# f1-control.net
KiCad netlist of a schematic drawn in EasyEDA Pro
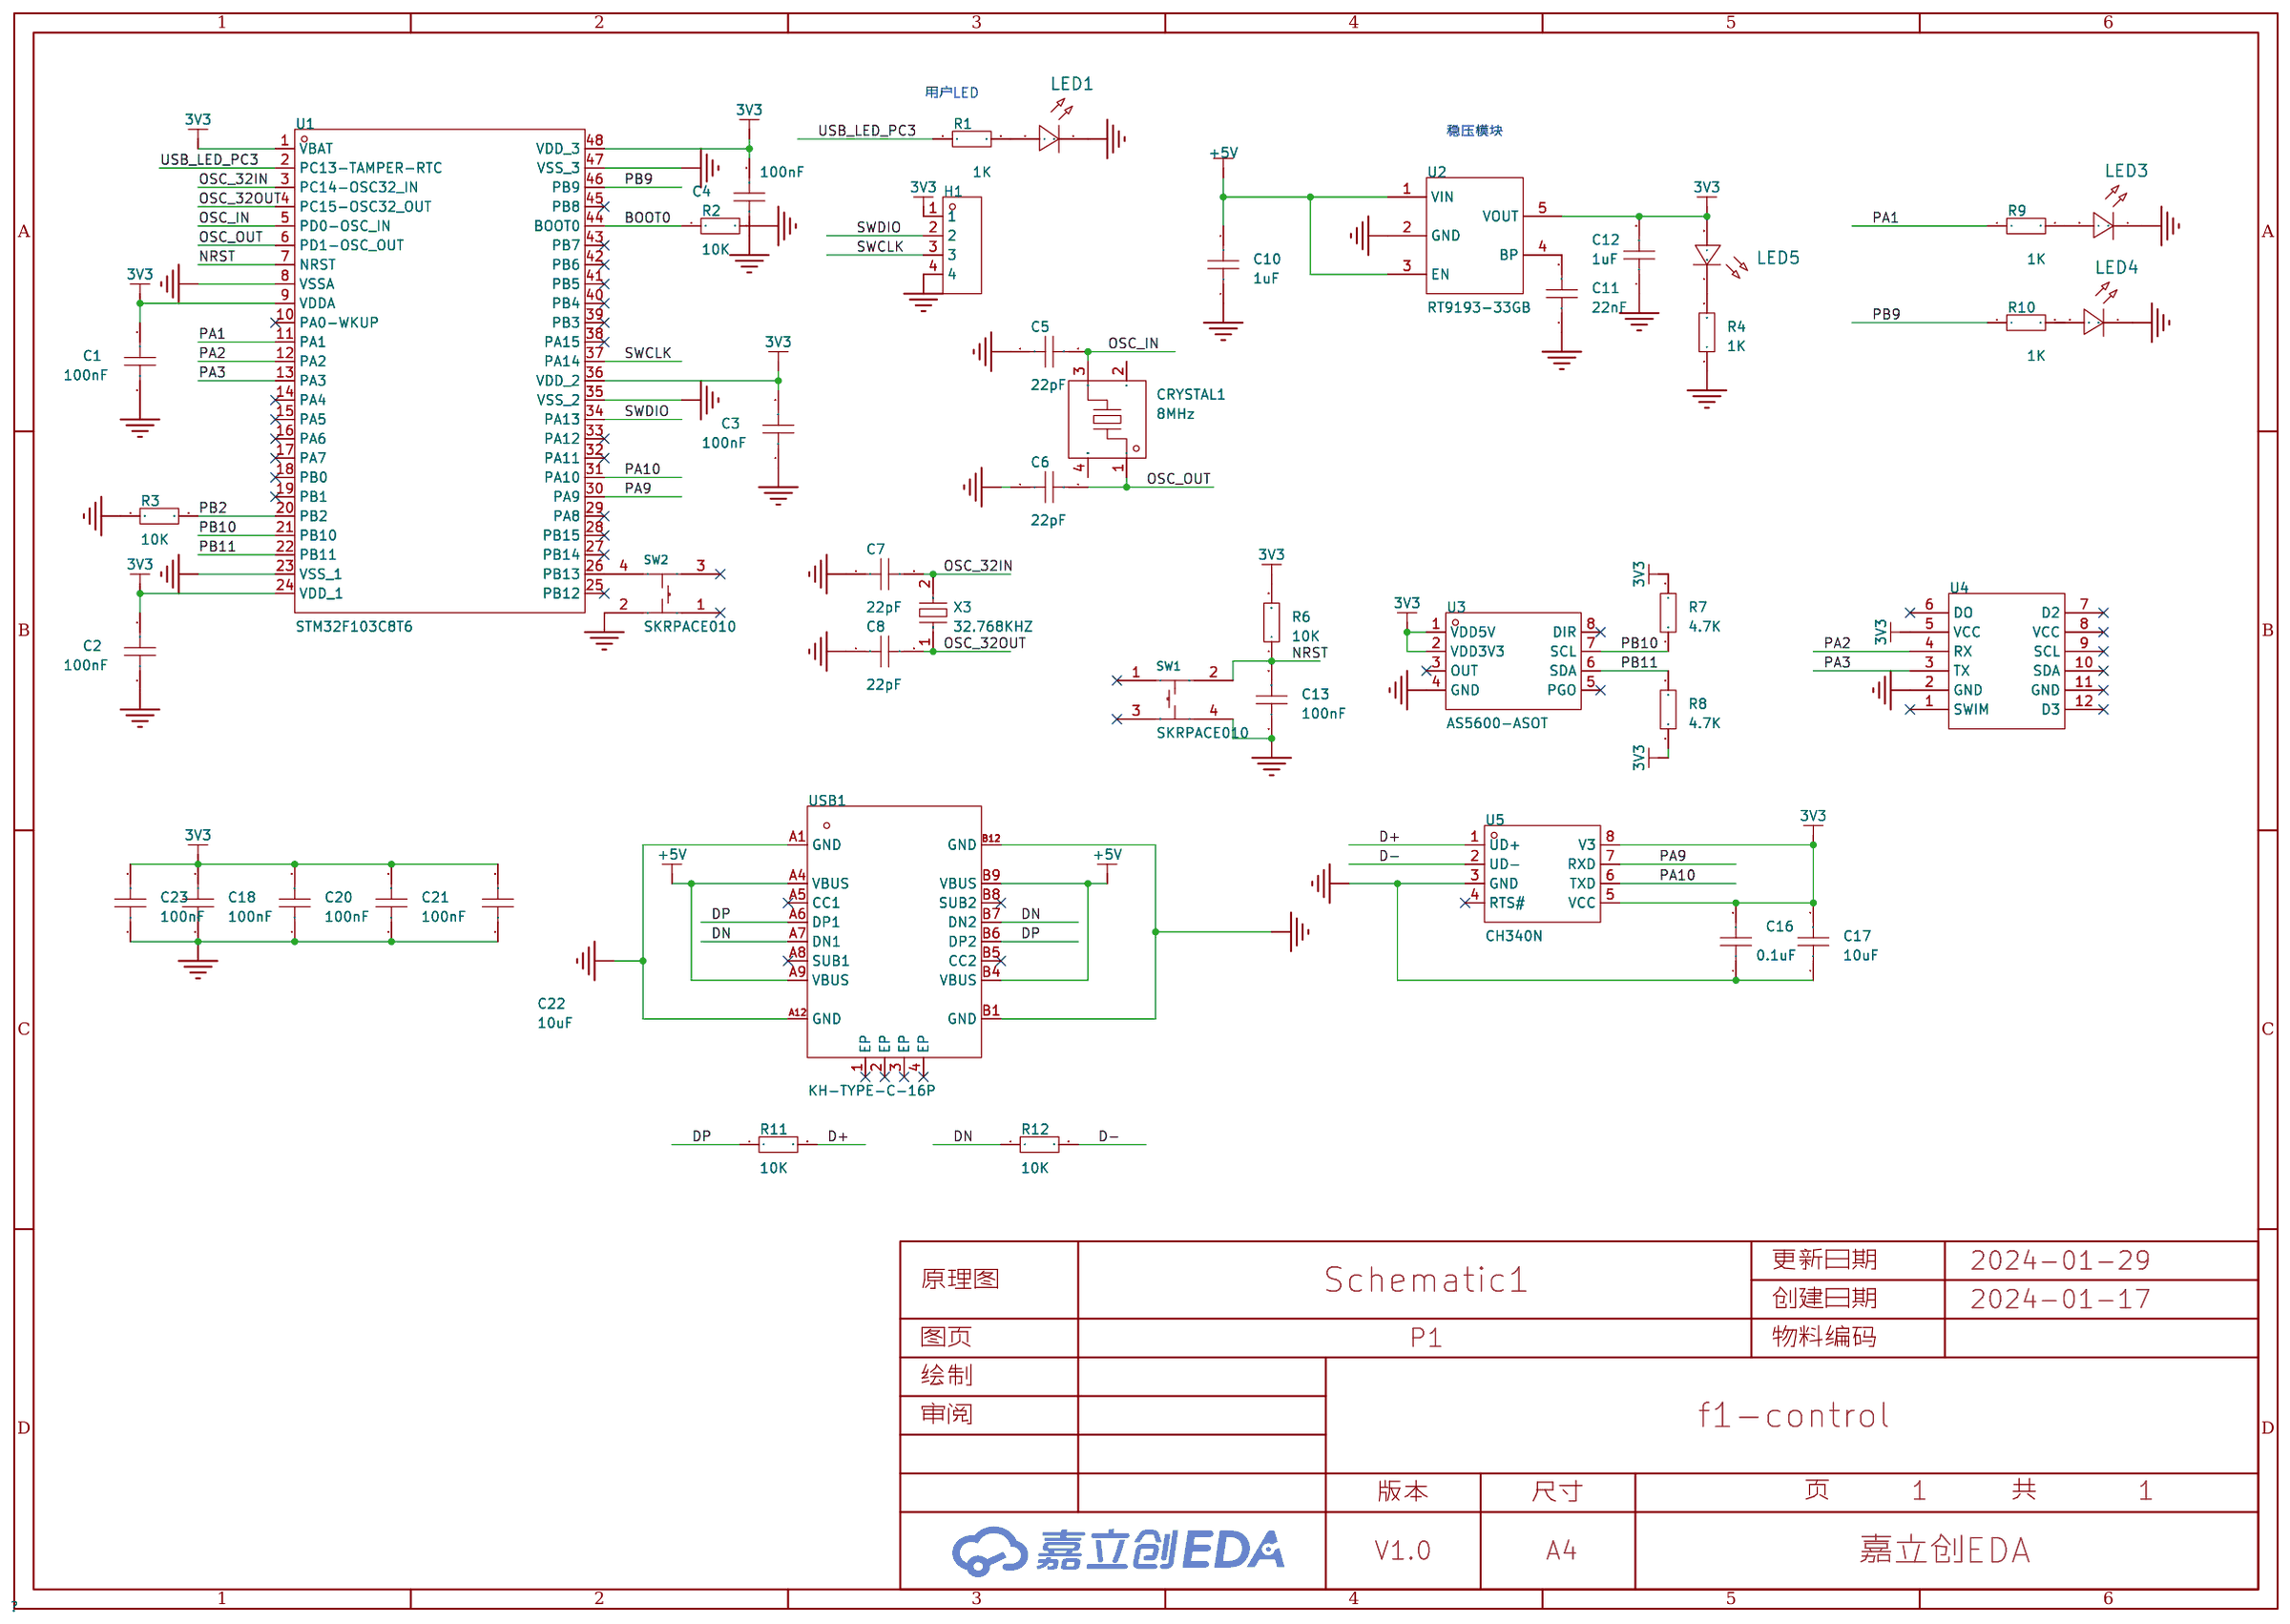
[diagram p0: schematic sheet]

(export (version "E")
  (design (tool "Eeschema 10.0.6"))
  (components
    (comp (ref "C1")
      (value "100nF")
      (footprint "easyedapro:C0603")
      (libsource (lib "easyedapro") (part "CapAcitance"))
    )
    (comp (ref "C2")
      (value "100nF")
      (footprint "easyedapro:C0603")
      (libsource (lib "easyedapro") (part "CapAcitance"))
    )
    (comp (ref "C3")
      (value "100nF")
      (footprint "easyedapro:C0603")
      (libsource (lib "easyedapro") (part "CapAcitance"))
    )
    (comp (ref "C4")
      (value "100nF")
      (footprint "easyedapro:C0603")
      (libsource (lib "easyedapro") (part "CapAcitance"))
    )
    (comp (ref "C5")
      (value "22pF")
      (footprint "easyedapro:C0603")
      (libsource (lib "easyedapro") (part "CapAcitance"))
    )
    (comp (ref "C6")
      (value "22pF")
      (footprint "easyedapro:C0603")
      (libsource (lib "easyedapro") (part "CapAcitance"))
    )
    (comp (ref "C7")
      (value "22pF")
      (footprint "easyedapro:C0603")
      (libsource (lib "easyedapro") (part "CapAcitance"))
    )
    (comp (ref "C8")
      (value "22pF")
      (footprint "easyedapro:C0603")
      (libsource (lib "easyedapro") (part "CapAcitance"))
    )
    (comp (ref "C10")
      (value "1uF")
      (footprint "easyedapro:C0603")
      (libsource (lib "easyedapro") (part "CapAcitance"))
    )
    (comp (ref "C11")
      (value "22nF")
      (footprint "easyedapro:C0603")
      (libsource (lib "easyedapro") (part "CapAcitance"))
    )
    (comp (ref "C12")
      (value "1uF")
      (footprint "easyedapro:C0603")
      (libsource (lib "easyedapro") (part "CapAcitance"))
    )
    (comp (ref "C13")
      (value "100nF")
      (footprint "easyedapro:C0603")
      (libsource (lib "easyedapro") (part "CapAcitance"))
    )
    (comp (ref "C16")
      (value "0.1uF")
      (footprint "easyedapro:C0603")
      (libsource (lib "easyedapro") (part "CapAcitance"))
    )
    (comp (ref "C17")
      (value "10uF")
      (footprint "easyedapro:C0603")
      (libsource (lib "easyedapro") (part "CapAcitance"))
    )
    (comp (ref "C18")
      (value "100nF")
      (footprint "easyedapro:C0603")
      (libsource (lib "easyedapro") (part "CapAcitance"))
    )
    (comp (ref "C20")
      (value "100nF")
      (footprint "easyedapro:C0603")
      (libsource (lib "easyedapro") (part "CapAcitance"))
    )
    (comp (ref "C21")
      (value "100nF")
      (footprint "easyedapro:C0603")
      (libsource (lib "easyedapro") (part "CapAcitance"))
    )
    (comp (ref "C22")
      (value "10uF")
      (footprint "easyedapro:C0603")
      (libsource (lib "easyedapro") (part "CapAcitance"))
    )
    (comp (ref "C23")
      (value "100nF")
      (footprint "easyedapro:C0603")
      (libsource (lib "easyedapro") (part "CapAcitance"))
    )
    (comp (ref "CRYSTAL1")
      (value "8MHz")
      (footprint "easyedapro:CRYSTAL-SMD_4P-L3.2-W2.5-BL_SIT8008BI")
      (description "晶振类型:贴片晶振;频率:8MHz;常温频差:±10ppm;外接负载电容:12pF;频率稳定度(全温):±30ppm;")
      (fields (field (name "Manufacturer Part") "CF4008M00012001") (field (name "Manufacturer") "HUAXIN(华昕)"))
      (libsource (lib "easyedapro") (part "CF4008M00012001"))
    )
    (comp (ref "H1")
      (value "~")
      (footprint "easyedapro:HDR-TH_4P-P2.54-V-F")
      (libsource (lib "easyedapro") (part "2.54-1*4P母"))
    )
    (comp (ref "LED1")
      (value "~")
      (footprint "easyedapro:LED_0603")
      (libsource (lib "easyedapro") (part "LED_R"))
    )
    (comp (ref "LED3")
      (value "~")
      (footprint "easyedapro:LED_0603")
      (libsource (lib "easyedapro") (part "LED_R"))
    )
    (comp (ref "LED4")
      (value "~")
      (footprint "easyedapro:LED_0603")
      (libsource (lib "easyedapro") (part "LED_R"))
    )
    (comp (ref "LED5")
      (value "~")
      (footprint "easyedapro:LED_0603")
      (libsource (lib "easyedapro") (part "LED_R"))
    )
    (comp (ref "R1") (value "1K") (footprint "easyedapro:R0603") (libsource (lib "easyedapro") (part "电阻")))
    (comp (ref "R2") (value "10K") (footprint "easyedapro:R0603") (libsource (lib "easyedapro") (part "电阻")))
    (comp (ref "R3") (value "10K") (footprint "easyedapro:R0603") (libsource (lib "easyedapro") (part "电阻")))
    (comp (ref "R4") (value "1K") (footprint "easyedapro:R0603") (libsource (lib "easyedapro") (part "电阻")))
    (comp (ref "R6") (value "10K") (footprint "easyedapro:R0603") (libsource (lib "easyedapro") (part "电阻")))
    (comp (ref "R7") (value "4.7K") (footprint "easyedapro:R0603") (libsource (lib "easyedapro") (part "电阻")))
    (comp (ref "R8") (value "4.7K") (footprint "easyedapro:R0603") (libsource (lib "easyedapro") (part "电阻")))
    (comp (ref "R9") (value "1K") (footprint "easyedapro:R0603") (libsource (lib "easyedapro") (part "电阻")))
    (comp (ref "R10") (value "1K") (footprint "easyedapro:R0603") (libsource (lib "easyedapro") (part "电阻")))
    (comp (ref "R11") (value "10K") (footprint "easyedapro:R0603") (libsource (lib "easyedapro") (part "电阻")))
    (comp (ref "R12") (value "10K") (footprint "easyedapro:R0603") (libsource (lib "easyedapro") (part "电阻")))
    (comp (ref "SW1")
      (value "SKRPACE010")
      (footprint "easyedapro:KEY-SMD_4P-L4.2-W3.2-P2.20-LS4.6")
      (description "触点电流:50mA;额定电压(DC):16V;电路结构:单刀单掷;安装方式:立贴;带灯:-;机械寿命:-;")
      (fields (field (name "Manufacturer") "ALPSALPINE(阿尔卑斯阿尔派)"))
      (libsource (lib "easyedapro") (part "SKRPACE010"))
    )
    (comp (ref "SW2")
      (value "SKRPACE010")
      (footprint "easyedapro:KEY-SMD_4P-L4.2-W3.2-P2.20-LS4.6")
      (description "触点电流:50mA;额定电压(DC):16V;电路结构:单刀单掷;安装方式:立贴;带灯:-;机械寿命:-;")
      (fields (field (name "Manufacturer") "ALPSALPINE(阿尔卑斯阿尔派)"))
      (libsource (lib "easyedapro") (part "SKRPACE010"))
    )
    (comp (ref "U1")
      (value "STM32F103C8T6")
      (footprint "easyedapro:LQFP-48_L7.0-W7.0-P0.50-LS9.0-BL")
      (fields (field (name "Manufacturer") "ST(意法半导体)"))
      (libsource (lib "easyedapro") (part "STM32F103C8T6"))
    )
    (comp (ref "U2")
      (value "RT9193-33GB")
      (footprint "easyedapro:SOT-23-5_L3.0-W1.7-P0.95-LS2.8-BL")
      (description "输出类型:固定;最大输入电压:5.5V;输出电压:3.3V;最大输出电流:300mA;电源纹波抑制比(PSRR):70dB;输出极性:正极;")
      (fields (field (name "Manufacturer") "RICHTEK(立锜)"))
      (libsource (lib "easyedapro") (part "RT9193-33GB"))
    )
    (comp (ref "U3")
      (value "AS5600-ASOT")
      (footprint "easyedapro:SOIC-8_L5.0-W4.0-P1.27-LS6.0-BL")
      (fields (field (name "Manufacturer") "ams(艾迈斯半导体)"))
      (libsource (lib "easyedapro") (part "AS5600-ASOT"))
    )
    (comp (ref "U4")
      (value "~")
      (footprint "easyedapro:WT901BC_TYL")
      (libsource (lib "easyedapro") (part "WT901BC_TYL"))
    )
    (comp (ref "U5")
      (value "CH340N")
      (footprint "easyedapro:SOP-8_L5.0-W4.0-P1.27-LS6.0-BL")
      (description "应用功能:-;接口协议:-;")
      (fields (field (name "Manufacturer") "WCH(南京沁恒)"))
      (libsource (lib "easyedapro") (part "CH340N"))
    )
    (comp (ref "USB1")
      (value "KH-TYPE-C-16P")
      (footprint "easyedapro:USB-C-SMD_KH-TYPE-C-16P")
      (description "连接器类型:Type-C;标准:-;公母:母;端口数量:1;触点数量:16P;安装方式:卧贴;额定电流 - 电源:3A;工作温度范围:-40°C~+85°C;")
      (fields (field (name "Manufacturer") "kinghelm(金航标)"))
      (libsource (lib "easyedapro") (part "KH-TYPE-C-16P"))
    )
    (comp (ref "X3")
      (value "32.768KHZ")
      (footprint "easyedapro:CRYSTAL-SMD_L3.2-W1.5-1")
      (libsource (lib "easyedapro") (part "32.768KHZ_C9900023773"))
    )
  )
  (nets
    (net (code "1") (name "+5V") (class "Default")
      (node (ref "C10") (pin "2") (pinfunction "2_2") (pintype "input"))
      (node (ref "U2") (pin "1") (pinfunction "VIN_1") (pintype "unspecified"))
      (node (ref "U2") (pin "3") (pinfunction "EN_3") (pintype "unspecified"))
      (node (ref "USB1") (pin "A4") (pinfunction "VBUS_A4") (pintype "unspecified"))
      (node (ref "USB1") (pin "A9") (pinfunction "VBUS_A9") (pintype "unspecified"))
      (node (ref "USB1") (pin "B4") (pinfunction "VBUS_B4") (pintype "unspecified"))
      (node (ref "USB1") (pin "B9") (pinfunction "VBUS_B9") (pintype "unspecified"))
    )
    (net (code "2") (name "/BOOT0") (class "Default")
      (node (ref "R2") (pin "1") (pinfunction "1_1") (pintype "input"))
      (node (ref "U1") (pin "44") (pinfunction "BOOT0_44") (pintype "unspecified"))
    )
    (net (code "3") (name "/D+") (class "Default")
      (node (ref "R11") (pin "2") (pinfunction "2_2") (pintype "input"))
      (node (ref "U5") (pin "1") (pinfunction "UD+_1") (pintype "unspecified"))
    )
    (net (code "4") (name "/D-") (class "Default")
      (node (ref "R12") (pin "2") (pinfunction "2_2") (pintype "input"))
      (node (ref "U5") (pin "2") (pinfunction "UD-_2") (pintype "unspecified"))
    )
    (net (code "5") (name "/DN") (class "Default")
      (node (ref "R12") (pin "1") (pinfunction "1_1") (pintype "input"))
      (node (ref "USB1") (pin "A7") (pinfunction "DN1_A7") (pintype "unspecified"))
      (node (ref "USB1") (pin "B7") (pinfunction "DN2_B7") (pintype "unspecified"))
    )
    (net (code "6") (name "/DP") (class "Default")
      (node (ref "R11") (pin "1") (pinfunction "1_1") (pintype "input"))
      (node (ref "USB1") (pin "A6") (pinfunction "DP1_A6") (pintype "unspecified"))
      (node (ref "USB1") (pin "B6") (pinfunction "DP2_B6") (pintype "unspecified"))
    )
    (net (code "7") (name "/NRST") (class "Default")
      (node (ref "C13") (pin "2") (pinfunction "2_2") (pintype "input"))
      (node (ref "R6") (pin "1") (pinfunction "1_1") (pintype "input"))
      (node (ref "SW1") (pin "2") (pinfunction "2_2") (pintype "input"))
      (node (ref "U1") (pin "7") (pinfunction "NRST_7") (pintype "unspecified"))
    )
    (net (code "8") (name "/OSC_32IN") (class "Default")
      (node (ref "C7") (pin "2") (pinfunction "2_2") (pintype "input"))
      (node (ref "U1") (pin "3") (pinfunction "PC14-OSC32_IN_3") (pintype "unspecified"))
      (node (ref "X3") (pin "2") (pinfunction "2_2") (pintype "input"))
    )
    (net (code "9") (name "/OSC_32OUT") (class "Default")
      (node (ref "C8") (pin "2") (pinfunction "2_2") (pintype "input"))
      (node (ref "U1") (pin "4") (pinfunction "PC15-OSC32_OUT_4") (pintype "unspecified"))
      (node (ref "X3") (pin "1") (pinfunction "1_1") (pintype "input"))
    )
    (net (code "10") (name "/OSC_IN") (class "Default")
      (node (ref "C5") (pin "2") (pinfunction "2_2") (pintype "input"))
      (node (ref "CRYSTAL1") (pin "3") (pinfunction "3_3") (pintype "input"))
      (node (ref "U1") (pin "5") (pinfunction "PD0-OSC_IN_5") (pintype "unspecified"))
    )
    (net (code "11") (name "/OSC_OUT") (class "Default")
      (node (ref "C6") (pin "2") (pinfunction "2_2") (pintype "input"))
      (node (ref "CRYSTAL1") (pin "1") (pinfunction "1_1") (pintype "input"))
      (node (ref "U1") (pin "6") (pinfunction "PD1-OSC_OUT_6") (pintype "unspecified"))
    )
    (net (code "12") (name "/PA1") (class "Default")
      (node (ref "R9") (pin "1") (pinfunction "1_1") (pintype "input"))
      (node (ref "U1") (pin "11") (pinfunction "PA1_11") (pintype "unspecified"))
    )
    (net (code "13") (name "/PA2") (class "Default")
      (node (ref "U1") (pin "12") (pinfunction "PA2_12") (pintype "unspecified"))
      (node (ref "U4") (pin "4") (pinfunction "RX_4") (pintype "input"))
    )
    (net (code "14") (name "/PA3") (class "Default")
      (node (ref "U1") (pin "13") (pinfunction "PA3_13") (pintype "unspecified"))
      (node (ref "U4") (pin "3") (pinfunction "TX_3") (pintype "input"))
    )
    (net (code "15") (name "/PA9") (class "Default")
      (node (ref "U1") (pin "30") (pinfunction "PA9_30") (pintype "unspecified"))
      (node (ref "U5") (pin "7") (pinfunction "RXD_7") (pintype "unspecified"))
    )
    (net (code "16") (name "/PA10") (class "Default")
      (node (ref "U1") (pin "31") (pinfunction "PA10_31") (pintype "unspecified"))
      (node (ref "U5") (pin "6") (pinfunction "TXD_6") (pintype "unspecified"))
    )
    (net (code "17") (name "/PB2") (class "Default")
      (node (ref "R3") (pin "2") (pinfunction "2_2") (pintype "input"))
      (node (ref "U1") (pin "20") (pinfunction "PB2_20") (pintype "unspecified"))
    )
    (net (code "18") (name "/PB9") (class "Default")
      (node (ref "R10") (pin "1") (pinfunction "1_1") (pintype "input"))
      (node (ref "U1") (pin "46") (pinfunction "PB9_46") (pintype "unspecified"))
    )
    (net (code "19") (name "/PB10") (class "Default")
      (node (ref "R7") (pin "1") (pinfunction "1_1") (pintype "input"))
      (node (ref "U1") (pin "21") (pinfunction "PB10_21") (pintype "unspecified"))
      (node (ref "U3") (pin "7") (pinfunction "SCL_7") (pintype "input"))
    )
    (net (code "20") (name "/PB11") (class "Default")
      (node (ref "R8") (pin "1") (pinfunction "1_1") (pintype "input"))
      (node (ref "U1") (pin "22") (pinfunction "PB11_22") (pintype "unspecified"))
      (node (ref "U3") (pin "6") (pinfunction "SDA_6") (pintype "input"))
    )
    (net (code "21") (name "/SWCLK") (class "Default")
      (node (ref "H1") (pin "3") (pinfunction "3_3") (pintype "unspecified"))
      (node (ref "U1") (pin "37") (pinfunction "PA14_37") (pintype "unspecified"))
    )
    (net (code "22") (name "/SWDIO") (class "Default")
      (node (ref "H1") (pin "2") (pinfunction "2_2") (pintype "unspecified"))
      (node (ref "U1") (pin "34") (pinfunction "PA13_34") (pintype "unspecified"))
    )
    (net (code "23") (name "/USB_LED_PC3") (class "Default")
      (node (ref "R1") (pin "1") (pinfunction "1_1") (pintype "input"))
      (node (ref "U1") (pin "2") (pinfunction "PC13-TAMPER-RTC_2") (pintype "unspecified"))
    )
    (net (code "24") (name "3V3") (class "Default")
      (node (ref "C1") (pin "2") (pinfunction "2_2") (pintype "input"))
      (node (ref "C12") (pin "2") (pinfunction "2_2") (pintype "input"))
      (node (ref "C16") (pin "2") (pinfunction "2_2") (pintype "input"))
      (node (ref "C17") (pin "2") (pinfunction "2_2") (pintype "input"))
      (node (ref "C18") (pin "2") (pinfunction "2_2") (pintype "input"))
      (node (ref "C2") (pin "2") (pinfunction "2_2") (pintype "input"))
      (node (ref "C20") (pin "2") (pinfunction "2_2") (pintype "input"))
      (node (ref "C21") (pin "2") (pinfunction "2_2") (pintype "input"))
      (node (ref "C22") (pin "2") (pinfunction "2_2") (pintype "input"))
      (node (ref "C23") (pin "2") (pinfunction "2_2") (pintype "input"))
      (node (ref "C3") (pin "2") (pinfunction "2_2") (pintype "input"))
      (node (ref "C4") (pin "2") (pinfunction "2_2") (pintype "input"))
      (node (ref "H1") (pin "1") (pinfunction "1_1") (pintype "unspecified"))
      (node (ref "LED5") (pin "2") (pinfunction "A_2") (pintype "input"))
      (node (ref "R6") (pin "2") (pinfunction "2_2") (pintype "input"))
      (node (ref "R7") (pin "2") (pinfunction "2_2") (pintype "input"))
      (node (ref "R8") (pin "2") (pinfunction "2_2") (pintype "input"))
      (node (ref "U1") (pin "1") (pinfunction "VBAT_1") (pintype "unspecified"))
      (node (ref "U1") (pin "24") (pinfunction "VDD_1_24") (pintype "unspecified"))
      (node (ref "U1") (pin "36") (pinfunction "VDD_2_36") (pintype "unspecified"))
      (node (ref "U1") (pin "48") (pinfunction "VDD_3_48") (pintype "unspecified"))
      (node (ref "U1") (pin "9") (pinfunction "VDDA_9") (pintype "unspecified"))
      (node (ref "U2") (pin "5") (pinfunction "VOUT_5") (pintype "unspecified"))
      (node (ref "U3") (pin "1") (pinfunction "VDD5V_1") (pintype "input"))
      (node (ref "U3") (pin "2") (pinfunction "VDD3V3_2") (pintype "input"))
      (node (ref "U4") (pin "5") (pinfunction "VCC_5") (pintype "input"))
      (node (ref "U5") (pin "5") (pinfunction "VCC_5") (pintype "unspecified"))
      (node (ref "U5") (pin "8") (pinfunction "V3_8") (pintype "unspecified"))
    )
    (net (code "25") (name "GND") (class "Default")
      (node (ref "C1") (pin "1") (pinfunction "1_1") (pintype "input"))
      (node (ref "C10") (pin "1") (pinfunction "1_1") (pintype "input"))
      (node (ref "C11") (pin "1") (pinfunction "1_1") (pintype "input"))
      (node (ref "C12") (pin "1") (pinfunction "1_1") (pintype "input"))
      (node (ref "C13") (pin "1") (pinfunction "1_1") (pintype "input"))
      (node (ref "C16") (pin "1") (pinfunction "1_1") (pintype "input"))
      (node (ref "C17") (pin "1") (pinfunction "1_1") (pintype "input"))
      (node (ref "C18") (pin "1") (pinfunction "1_1") (pintype "input"))
      (node (ref "C2") (pin "1") (pinfunction "1_1") (pintype "input"))
      (node (ref "C20") (pin "1") (pinfunction "1_1") (pintype "input"))
      (node (ref "C21") (pin "1") (pinfunction "1_1") (pintype "input"))
      (node (ref "C22") (pin "1") (pinfunction "1_1") (pintype "input"))
      (node (ref "C23") (pin "1") (pinfunction "1_1") (pintype "input"))
      (node (ref "C3") (pin "1") (pinfunction "1_1") (pintype "input"))
      (node (ref "C4") (pin "1") (pinfunction "1_1") (pintype "input"))
      (node (ref "C5") (pin "1") (pinfunction "1_1") (pintype "input"))
      (node (ref "C6") (pin "1") (pinfunction "1_1") (pintype "input"))
      (node (ref "C7") (pin "1") (pinfunction "1_1") (pintype "input"))
      (node (ref "C8") (pin "1") (pinfunction "1_1") (pintype "input"))
      (node (ref "H1") (pin "4") (pinfunction "4_4") (pintype "unspecified"))
      (node (ref "LED1") (pin "1") (pinfunction "C_1") (pintype "input"))
      (node (ref "LED3") (pin "1") (pinfunction "C_1") (pintype "input"))
      (node (ref "LED4") (pin "1") (pinfunction "C_1") (pintype "input"))
      (node (ref "R2") (pin "2") (pinfunction "2_2") (pintype "input"))
      (node (ref "R3") (pin "1") (pinfunction "1_1") (pintype "input"))
      (node (ref "R4") (pin "1") (pinfunction "1_1") (pintype "input"))
      (node (ref "SW1") (pin "4") (pinfunction "4_4") (pintype "input"))
      (node (ref "SW2") (pin "2") (pinfunction "2_2") (pintype "input"))
      (node (ref "U1") (pin "23") (pinfunction "VSS_1_23") (pintype "unspecified"))
      (node (ref "U1") (pin "35") (pinfunction "VSS_2_35") (pintype "unspecified"))
      (node (ref "U1") (pin "47") (pinfunction "VSS_3_47") (pintype "unspecified"))
      (node (ref "U1") (pin "8") (pinfunction "VSSA_8") (pintype "unspecified"))
      (node (ref "U2") (pin "2") (pinfunction "GND_2") (pintype "unspecified"))
      (node (ref "U3") (pin "4") (pinfunction "GND_4") (pintype "input"))
      (node (ref "U4") (pin "2") (pinfunction "GND_2") (pintype "input"))
      (node (ref "U5") (pin "3") (pinfunction "GND_3") (pintype "unspecified"))
      (node (ref "USB1") (pin "A1") (pinfunction "GND_A1") (pintype "unspecified"))
      (node (ref "USB1") (pin "A12") (pinfunction "GND_A12") (pintype "unspecified"))
      (node (ref "USB1") (pin "B1") (pinfunction "GND_B1") (pintype "unspecified"))
      (node (ref "USB1") (pin "B12") (pinfunction "GND_B12") (pintype "unspecified"))
    )
    (net (code "26") (name "Net-(LED1-A)") (class "Default")
      (node (ref "LED1") (pin "2") (pinfunction "A_2") (pintype "input"))
      (node (ref "R1") (pin "2") (pinfunction "2_2") (pintype "input"))
    )
    (net (code "27") (name "Net-(LED3-A)") (class "Default")
      (node (ref "LED3") (pin "2") (pinfunction "A_2") (pintype "input"))
      (node (ref "R9") (pin "2") (pinfunction "2_2") (pintype "input"))
    )
    (net (code "28") (name "Net-(LED4-A)") (class "Default")
      (node (ref "LED4") (pin "2") (pinfunction "A_2") (pintype "input"))
      (node (ref "R10") (pin "2") (pinfunction "2_2") (pintype "input"))
    )
    (net (code "29") (name "Net-(LED5-C)") (class "Default")
      (node (ref "LED5") (pin "1") (pinfunction "C_1") (pintype "input"))
      (node (ref "R4") (pin "2") (pinfunction "2_2") (pintype "input"))
    )
    (net (code "30") (name "Net-(U1-PB13)") (class "Default")
      (node (ref "SW2") (pin "4") (pinfunction "4_4") (pintype "input"))
      (node (ref "U1") (pin "26") (pinfunction "PB13_26") (pintype "unspecified"))
    )
    (net (code "31") (name "Net-(U2-BP)") (class "Default")
      (node (ref "C11") (pin "2") (pinfunction "2_2") (pintype "input"))
      (node (ref "U2") (pin "4") (pinfunction "BP_4") (pintype "unspecified"))
    )
    (net (code "32") (name "unconnected-(CRYSTAL1-GND-Pad2)") (class "Default")
      (node (ref "CRYSTAL1") (pin "2") (pinfunction "GND_2") (pintype "input"))
    )
    (net (code "33") (name "unconnected-(CRYSTAL1-GND-Pad4)") (class "Default")
      (node (ref "CRYSTAL1") (pin "4") (pinfunction "GND_4") (pintype "input"))
    )
    (net (code "34") (name "unconnected-(SW1-Pad1)") (class "Default")
      (node (ref "SW1") (pin "1") (pinfunction "1_1") (pintype "input+no_connect"))
    )
    (net (code "35") (name "unconnected-(SW1-Pad3)") (class "Default")
      (node (ref "SW1") (pin "3") (pinfunction "3_3") (pintype "input+no_connect"))
    )
    (net (code "36") (name "unconnected-(SW2-Pad1)") (class "Default")
      (node (ref "SW2") (pin "1") (pinfunction "1_1") (pintype "input+no_connect"))
    )
    (net (code "37") (name "unconnected-(SW2-Pad3)") (class "Default")
      (node (ref "SW2") (pin "3") (pinfunction "3_3") (pintype "input+no_connect"))
    )
    (net (code "38") (name "unconnected-(U1-PA0-WKUP-Pad10)") (class "Default")
      (node (ref "U1") (pin "10") (pinfunction "PA0-WKUP_10") (pintype "unspecified+no_connect"))
    )
    (net (code "39") (name "unconnected-(U1-PA4-Pad14)") (class "Default")
      (node (ref "U1") (pin "14") (pinfunction "PA4_14") (pintype "unspecified+no_connect"))
    )
    (net (code "40") (name "unconnected-(U1-PA5-Pad15)") (class "Default")
      (node (ref "U1") (pin "15") (pinfunction "PA5_15") (pintype "unspecified+no_connect"))
    )
    (net (code "41") (name "unconnected-(U1-PA6-Pad16)") (class "Default")
      (node (ref "U1") (pin "16") (pinfunction "PA6_16") (pintype "unspecified+no_connect"))
    )
    (net (code "42") (name "unconnected-(U1-PA7-Pad17)") (class "Default")
      (node (ref "U1") (pin "17") (pinfunction "PA7_17") (pintype "unspecified+no_connect"))
    )
    (net (code "43") (name "unconnected-(U1-PA8-Pad29)") (class "Default")
      (node (ref "U1") (pin "29") (pinfunction "PA8_29") (pintype "unspecified+no_connect"))
    )
    (net (code "44") (name "unconnected-(U1-PA11-Pad32)") (class "Default")
      (node (ref "U1") (pin "32") (pinfunction "PA11_32") (pintype "unspecified+no_connect"))
    )
    (net (code "45") (name "unconnected-(U1-PA12-Pad33)") (class "Default")
      (node (ref "U1") (pin "33") (pinfunction "PA12_33") (pintype "unspecified+no_connect"))
    )
    (net (code "46") (name "unconnected-(U1-PA15-Pad38)") (class "Default")
      (node (ref "U1") (pin "38") (pinfunction "PA15_38") (pintype "unspecified+no_connect"))
    )
    (net (code "47") (name "unconnected-(U1-PB0-Pad18)") (class "Default")
      (node (ref "U1") (pin "18") (pinfunction "PB0_18") (pintype "unspecified+no_connect"))
    )
    (net (code "48") (name "unconnected-(U1-PB1-Pad19)") (class "Default")
      (node (ref "U1") (pin "19") (pinfunction "PB1_19") (pintype "unspecified+no_connect"))
    )
    (net (code "49") (name "unconnected-(U1-PB3-Pad39)") (class "Default")
      (node (ref "U1") (pin "39") (pinfunction "PB3_39") (pintype "unspecified+no_connect"))
    )
    (net (code "50") (name "unconnected-(U1-PB4-Pad40)") (class "Default")
      (node (ref "U1") (pin "40") (pinfunction "PB4_40") (pintype "unspecified+no_connect"))
    )
    (net (code "51") (name "unconnected-(U1-PB5-Pad41)") (class "Default")
      (node (ref "U1") (pin "41") (pinfunction "PB5_41") (pintype "unspecified+no_connect"))
    )
    (net (code "52") (name "unconnected-(U1-PB6-Pad42)") (class "Default")
      (node (ref "U1") (pin "42") (pinfunction "PB6_42") (pintype "unspecified+no_connect"))
    )
    (net (code "53") (name "unconnected-(U1-PB7-Pad43)") (class "Default")
      (node (ref "U1") (pin "43") (pinfunction "PB7_43") (pintype "unspecified+no_connect"))
    )
    (net (code "54") (name "unconnected-(U1-PB8-Pad45)") (class "Default")
      (node (ref "U1") (pin "45") (pinfunction "PB8_45") (pintype "unspecified+no_connect"))
    )
    (net (code "55") (name "unconnected-(U1-PB12-Pad25)") (class "Default")
      (node (ref "U1") (pin "25") (pinfunction "PB12_25") (pintype "unspecified+no_connect"))
    )
    (net (code "56") (name "unconnected-(U1-PB14-Pad27)") (class "Default")
      (node (ref "U1") (pin "27") (pinfunction "PB14_27") (pintype "unspecified+no_connect"))
    )
    (net (code "57") (name "unconnected-(U1-PB15-Pad28)") (class "Default")
      (node (ref "U1") (pin "28") (pinfunction "PB15_28") (pintype "unspecified+no_connect"))
    )
    (net (code "58") (name "unconnected-(U3-DIR-Pad8)") (class "Default")
      (node (ref "U3") (pin "8") (pinfunction "DIR_8") (pintype "input+no_connect"))
    )
    (net (code "59") (name "unconnected-(U3-OUT-Pad3)") (class "Default")
      (node (ref "U3") (pin "3") (pinfunction "OUT_3") (pintype "input+no_connect"))
    )
    (net (code "60") (name "unconnected-(U3-PGO-Pad5)") (class "Default")
      (node (ref "U3") (pin "5") (pinfunction "PGO_5") (pintype "input+no_connect"))
    )
    (net (code "61") (name "unconnected-(U4-D2-Pad7)") (class "Default")
      (node (ref "U4") (pin "7") (pinfunction "D2_7") (pintype "input+no_connect"))
    )
    (net (code "62") (name "unconnected-(U4-D3-Pad12)") (class "Default")
      (node (ref "U4") (pin "12") (pinfunction "D3_12") (pintype "input+no_connect"))
    )
    (net (code "63") (name "unconnected-(U4-DO-Pad6)") (class "Default")
      (node (ref "U4") (pin "6") (pinfunction "DO_6") (pintype "input+no_connect"))
    )
    (net (code "64") (name "unconnected-(U4-GND-Pad11)") (class "Default")
      (node (ref "U4") (pin "11") (pinfunction "GND_11") (pintype "input+no_connect"))
    )
    (net (code "65") (name "unconnected-(U4-SCL-Pad9)") (class "Default")
      (node (ref "U4") (pin "9") (pinfunction "SCL_9") (pintype "input+no_connect"))
    )
    (net (code "66") (name "unconnected-(U4-SDA-Pad10)") (class "Default")
      (node (ref "U4") (pin "10") (pinfunction "SDA_10") (pintype "input+no_connect"))
    )
    (net (code "67") (name "unconnected-(U4-SWIM-Pad1)") (class "Default")
      (node (ref "U4") (pin "1") (pinfunction "SWIM_1") (pintype "input+no_connect"))
    )
    (net (code "68") (name "unconnected-(U4-VCC-Pad8)") (class "Default")
      (node (ref "U4") (pin "8") (pinfunction "VCC_8") (pintype "input+no_connect"))
    )
    (net (code "69") (name "unconnected-(U5-RTS#-Pad4)") (class "Default")
      (node (ref "U5") (pin "4") (pinfunction "RTS#_4") (pintype "unspecified+no_connect"))
    )
    (net (code "70") (name "unconnected-(USB1-CC1-PadA5)") (class "Default")
      (node (ref "USB1") (pin "A5") (pinfunction "CC1_A5") (pintype "unspecified+no_connect"))
    )
    (net (code "71") (name "unconnected-(USB1-CC2-PadB5)") (class "Default")
      (node (ref "USB1") (pin "B5") (pinfunction "CC2_B5") (pintype "unspecified+no_connect"))
    )
    (net (code "72") (name "unconnected-(USB1-EP-Pad1)") (class "Default")
      (node (ref "USB1") (pin "1") (pinfunction "EP_1") (pintype "unspecified+no_connect"))
    )
    (net (code "73") (name "unconnected-(USB1-EP-Pad2)") (class "Default")
      (node (ref "USB1") (pin "2") (pinfunction "EP_2") (pintype "unspecified+no_connect"))
    )
    (net (code "74") (name "unconnected-(USB1-EP-Pad3)") (class "Default")
      (node (ref "USB1") (pin "3") (pinfunction "EP_3") (pintype "unspecified+no_connect"))
    )
    (net (code "75") (name "unconnected-(USB1-EP-Pad4)") (class "Default")
      (node (ref "USB1") (pin "4") (pinfunction "EP_4") (pintype "unspecified+no_connect"))
    )
    (net (code "76") (name "unconnected-(USB1-SUB1-PadA8)") (class "Default")
      (node (ref "USB1") (pin "A8") (pinfunction "SUB1_A8") (pintype "unspecified+no_connect"))
    )
    (net (code "77") (name "unconnected-(USB1-SUB2-PadB8)") (class "Default")
      (node (ref "USB1") (pin "B8") (pinfunction "SUB2_B8") (pintype "unspecified+no_connect"))
    )
  )
)
